# main.net
KiCad netlist of a schematic drawn in Altium Designer
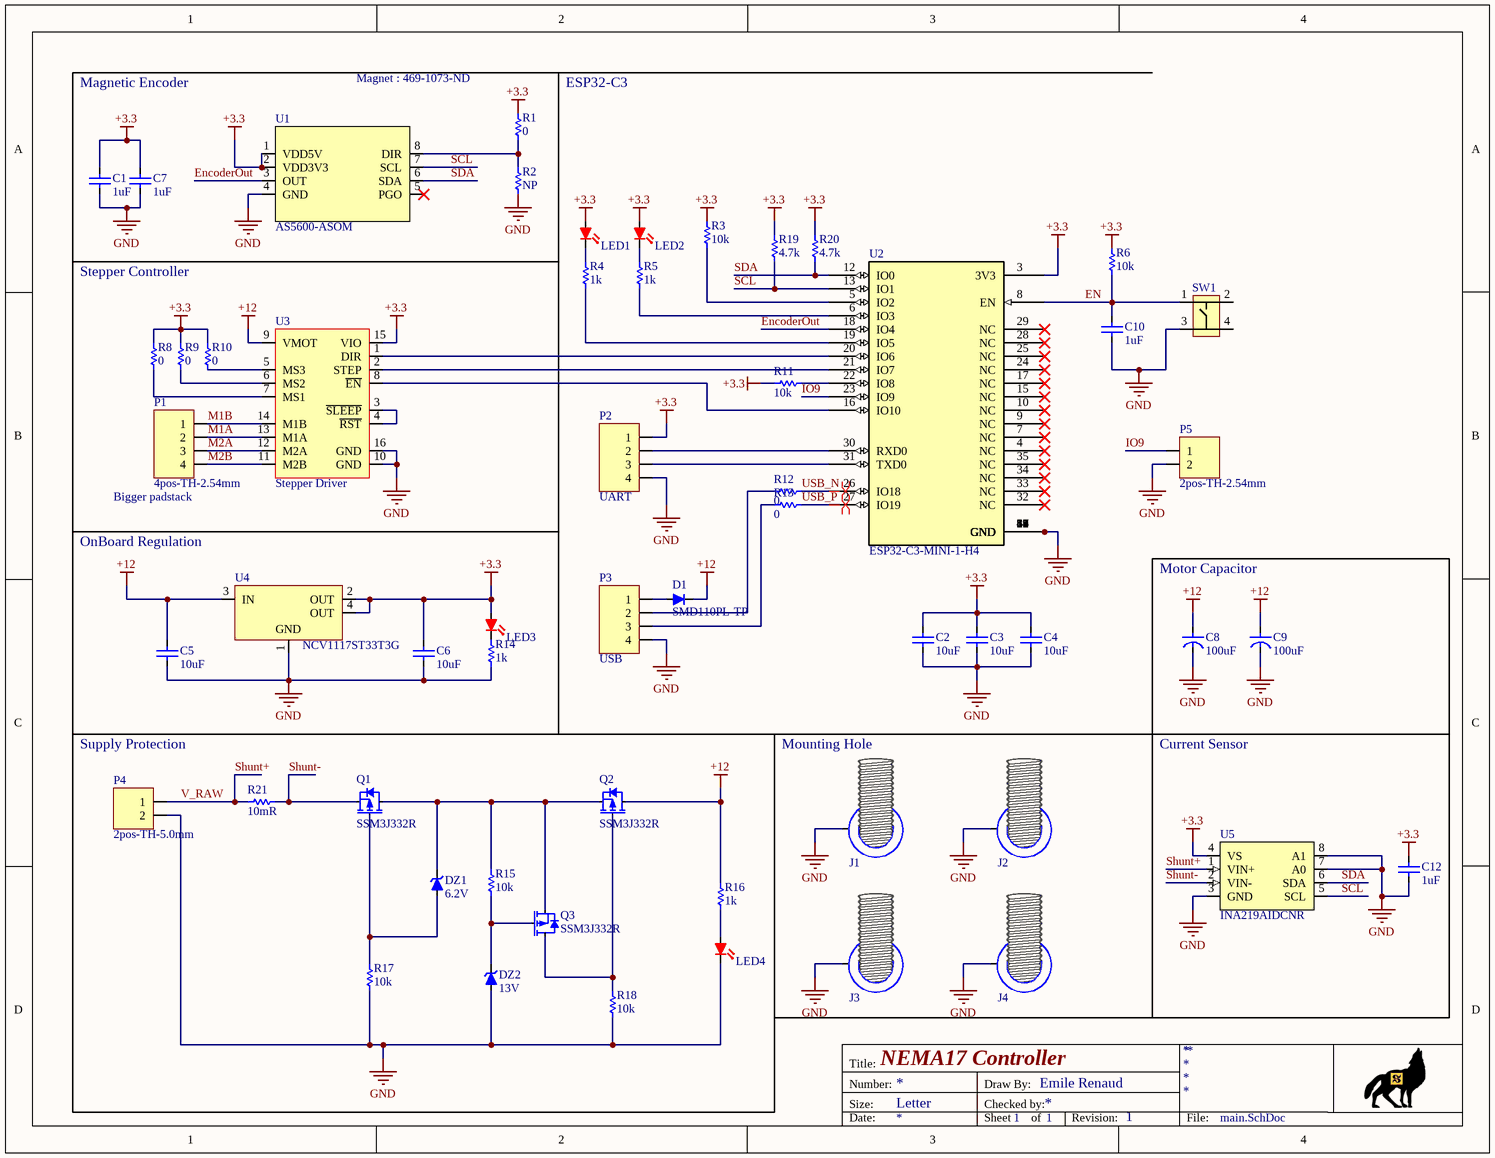
[diagram p0: main.SchDoc]

(export (version "E")
  (design (tool "Eeschema 10.0.6"))
  (components
    (comp (ref "C1")
      (value "1uF")
      (footprint "CAPACITOR-0603")
      (description "Capacitor-0603-1uF-25V-X5R")
      (libsource (lib "Capacitors") (part "Capacitor-0603-1uF-25V-X5R"))
    )
    (comp (ref "C2")
      (value "10uF")
      (footprint "CAPACITOR-0805")
      (description "Capacitor-0805-10uF-35V-X5R")
      (libsource (lib "Capacitors") (part "Capacitor-0805-10uF-35V-X5R"))
    )
    (comp (ref "C3")
      (value "10uF")
      (footprint "CAPACITOR-0805")
      (description "Capacitor-0805-10uF-35V-X5R")
      (libsource (lib "Capacitors") (part "Capacitor-0805-10uF-35V-X5R"))
    )
    (comp (ref "C4")
      (value "10uF")
      (footprint "CAPACITOR-0805")
      (description "Capacitor-0805-10uF-35V-X5R")
      (libsource (lib "Capacitors") (part "Capacitor-0805-10uF-35V-X5R"))
    )
    (comp (ref "C5")
      (value "10uF")
      (footprint "CAPACITOR-0805")
      (description "Capacitor-0805-10uF-35V-X5R")
      (libsource (lib "Capacitors") (part "Capacitor-0805-10uF-35V-X5R"))
    )
    (comp (ref "C6")
      (value "10uF")
      (footprint "CAPACITOR-0805")
      (description "Capacitor-0805-10uF-35V-X5R")
      (libsource (lib "Capacitors") (part "Capacitor-0805-10uF-35V-X5R"))
    )
    (comp (ref "C7")
      (value "1uF")
      (footprint "CAPACITOR-0603")
      (description "Capacitor-0603-1uF-25V-X5R")
      (libsource (lib "Capacitors") (part "Capacitor-0603-1uF-25V-X5R"))
    )
    (comp (ref "C8")
      (value "100uF")
      (footprint "CAPACITOR-Aluminium-5x11mm-2mmPitch")
      (description "CAP ALUM 100UF 20% 25V RADIAL")
      (libsource (lib "Capacitors-Electrolytic") (part "Capacitor-100uF-25V"))
    )
    (comp (ref "C9")
      (value "100uF")
      (footprint "CAPACITOR-Aluminium-5x11mm-2mmPitch")
      (description "CAP ALUM 100UF 20% 25V RADIAL")
      (libsource (lib "Capacitors-Electrolytic") (part "Capacitor-100uF-25V"))
    )
    (comp (ref "C10")
      (value "1uF")
      (footprint "CAPACITOR-0603")
      (description "Capacitor-0603-1uF-25V-X5R")
      (libsource (lib "Capacitors") (part "Capacitor-0603-1uF-25V-X5R"))
    )
    (comp (ref "C12")
      (value "1uF")
      (footprint "CAPACITOR-0603")
      (description "Capacitor-0603-1uF-25V-X5R")
      (libsource (lib "Capacitors") (part "Capacitor-0603-1uF-25V-X5R"))
    )
    (comp (ref "D1")
      (value "SMD110PL-TP")
      (footprint "SOD-123F")
      (description "DIODE SCHOTTKY 100V 1A SOD123FL")
      (libsource (lib "diodes") (part "SMD110PL-TP"))
    )
    (comp (ref "DZ1")
      (value "BZT52C6V2-TP")
      (footprint "SOD-123")
      (description "Zener Diode 6.2 V 200 mW ±6% Surface Mount SOD-123")
      (fields (field (name "VOLT") "6.2V"))
      (libsource (lib "diodes-zener") (part "BZT52C6V2-TP"))
    )
    (comp (ref "DZ2")
      (value "BZT52C13-TP")
      (footprint "SOD-123")
      (description "Zener Diode 13 V 200 mW ±6% Surface Mount SOD-123")
      (fields (field (name "VOLT") "13V"))
      (libsource (lib "diodes-zener") (part "BZT52C13-TP"))
    )
    (comp (ref "J1")
      (value "hole")
      (footprint "HOLE-3.40MM-M3-8MMEYELET")
      (description "Hole for M3 Bolt with 8mm pad")
      (libsource (lib "JumpersAndHoles") (part "Hole 3.40mm M3-Eyelet"))
    )
    (comp (ref "J2")
      (value "hole")
      (footprint "HOLE-3.40MM-M3-8MMEYELET")
      (description "Hole for M3 Bolt with 8mm pad")
      (libsource (lib "JumpersAndHoles") (part "Hole 3.40mm M3-Eyelet"))
    )
    (comp (ref "J3")
      (value "hole")
      (footprint "HOLE-3.40MM-M3-8MMEYELET")
      (description "Hole for M3 Bolt with 8mm pad")
      (libsource (lib "JumpersAndHoles") (part "Hole 3.40mm M3-Eyelet"))
    )
    (comp (ref "J4")
      (value "hole")
      (footprint "HOLE-3.40MM-M3-8MMEYELET")
      (description "Hole for M3 Bolt with 8mm pad")
      (libsource (lib "JumpersAndHoles") (part "Hole 3.40mm M3-Eyelet"))
    )
    (comp (ref "LED1")
      (value "B1911USD-20D000114U1930")
      (footprint "LED-0603-2PIN")
      (description "LED RED CLEAR 1608 SMD")
      (libsource (lib "LEDs") (part "B1911USD-20D000114U1930"))
    )
    (comp (ref "LED2")
      (value "B1911USD-20D000114U1930")
      (footprint "LED-0603-2PIN")
      (description "LED RED CLEAR 1608 SMD")
      (libsource (lib "LEDs") (part "B1911USD-20D000114U1930"))
    )
    (comp (ref "LED3")
      (value "B1911USD-20D000114U1930")
      (footprint "LED-0603-2PIN")
      (description "LED RED CLEAR 1608 SMD")
      (libsource (lib "LEDs") (part "B1911USD-20D000114U1930"))
    )
    (comp (ref "LED4")
      (value "B1911USD-20D000114U1930")
      (footprint "LED-0603-2PIN")
      (description "LED RED CLEAR 1608 SMD")
      (libsource (lib "LEDs") (part "B1911USD-20D000114U1930"))
    )
    (comp (ref "P1")
      (value "4pos-TH-2.54mm")
      (footprint "HDR1X4-W")
      (description "4pos TH 2.54mm Header")
      (libsource (lib "header") (part "4pos-TH-2.54mm"))
    )
    (comp (ref "P2")
      (value "UART")
      (footprint "HDR1X4")
      (description "4pos TH 2.54mm Header")
      (libsource (lib "header") (part "4pos-TH-2.54mm"))
    )
    (comp (ref "P3")
      (value "USB")
      (footprint "HDR1X4")
      (description "4pos TH 2.54mm Header")
      (libsource (lib "header") (part "4pos-TH-2.54mm"))
    )
    (comp (ref "P4")
      (value "2pos-TH-5.0mm")
      (footprint "Weco 2")
      (description "2pos-TH-5.0mm Screw Terminal")
      (libsource (lib "ScrewTerminal") (part "2pos-TH-5.0mm"))
    )
    (comp (ref "P5")
      (value "2pos-TH-2.54mm")
      (footprint "HDR1X2")
      (description "2pos TH 2.54mm Header")
      (libsource (lib "header") (part "2pos-TH-2.54mm"))
    )
    (comp (ref "Q1")
      (value "SSM3J332R")
      (footprint "SOT-23-3")
      (description "P-Channel 30 V 6A (Ta) 1W (Ta) Surface Mount SOT-23F")
      (libsource (lib "FET-P-Small") (part "SSM3J332R"))
    )
    (comp (ref "Q2")
      (value "SSM3J332R")
      (footprint "SOT-23-3")
      (description "P-Channel 30 V 6A (Ta) 1W (Ta) Surface Mount SOT-23F")
      (libsource (lib "FET-P-Small") (part "SSM3J332R"))
    )
    (comp (ref "Q3")
      (value "SSM3J332R")
      (footprint "SOT-23-3")
      (description "P-Channel 30 V 6A (Ta) 1W (Ta) Surface Mount SOT-23F")
      (libsource (lib "FET-P-Small") (part "SSM3J332R"))
    )
    (comp (ref "R1")
      (value "0")
      (footprint "Resistor-0603")
      (description "Resistor0603-0.0")
      (fields (field (name "Comment") "SMT resistor"))
      (libsource (lib "Resistors") (part "Resistor0603-0.0"))
    )
    (comp (ref "R2")
      (value "NP")
      (footprint "Resistor-0603")
      (description "Resistor0603-0.0")
      (fields (field (name "Comment") "SMT resistor"))
      (libsource (lib "Resistors") (part "Resistor0603-0.0"))
    )
    (comp (ref "R3")
      (value "10k")
      (footprint "Resistor-0603")
      (description "Resistor0603-10k")
      (fields (field (name "Comment") "SMT resistor"))
      (libsource (lib "Resistors") (part "Resistor0603-10k"))
    )
    (comp (ref "R4")
      (value "1k")
      (footprint "Resistor-0603")
      (description "Resistor0603-1k")
      (fields (field (name "Comment") "SMT resistor"))
      (libsource (lib "Resistors") (part "Resistor0603-1k"))
    )
    (comp (ref "R5")
      (value "1k")
      (footprint "Resistor-0603")
      (description "Resistor0603-1k")
      (fields (field (name "Comment") "SMT resistor"))
      (libsource (lib "Resistors") (part "Resistor0603-1k"))
    )
    (comp (ref "R6")
      (value "10k")
      (footprint "Resistor-0603")
      (description "Resistor0603-10k")
      (fields (field (name "Comment") "SMT resistor"))
      (libsource (lib "Resistors") (part "Resistor0603-10k"))
    )
    (comp (ref "R8")
      (value "0")
      (footprint "Resistor-0603")
      (description "Resistor0603-0.0")
      (fields (field (name "Comment") "SMT resistor"))
      (libsource (lib "Resistors") (part "Resistor0603-0.0"))
    )
    (comp (ref "R9")
      (value "0")
      (footprint "Resistor-0603")
      (description "Resistor0603-0.0")
      (fields (field (name "Comment") "SMT resistor"))
      (libsource (lib "Resistors") (part "Resistor0603-0.0"))
    )
    (comp (ref "R10")
      (value "0")
      (footprint "Resistor-0603")
      (description "Resistor0603-0.0")
      (fields (field (name "Comment") "SMT resistor"))
      (libsource (lib "Resistors") (part "Resistor0603-0.0"))
    )
    (comp (ref "R11")
      (value "10k")
      (footprint "Resistor-0603")
      (description "Resistor0603-10k")
      (fields (field (name "Comment") "SMT resistor"))
      (libsource (lib "Resistors") (part "Resistor0603-10k"))
    )
    (comp (ref "R12")
      (value "0")
      (footprint "Resistor-0603")
      (description "Resistor0603-0.0")
      (fields (field (name "Comment") "SMT resistor"))
      (libsource (lib "Resistors") (part "Resistor0603-0.0"))
    )
    (comp (ref "R13")
      (value "0")
      (footprint "Resistor-0603")
      (description "Resistor0603-0.0")
      (fields (field (name "Comment") "SMT resistor"))
      (libsource (lib "Resistors") (part "Resistor0603-0.0"))
    )
    (comp (ref "R14")
      (value "1k")
      (footprint "Resistor-0603")
      (description "Resistor0603-1k")
      (fields (field (name "Comment") "SMT resistor"))
      (libsource (lib "Resistors") (part "Resistor0603-1k"))
    )
    (comp (ref "R15")
      (value "10k")
      (footprint "Resistor-0603")
      (description "Resistor0603-10k")
      (fields (field (name "Comment") "SMT resistor"))
      (libsource (lib "Resistors") (part "Resistor0603-10k"))
    )
    (comp (ref "R16")
      (value "1k")
      (footprint "Resistor-0603")
      (description "Resistor0603-1k")
      (fields (field (name "Comment") "SMT resistor"))
      (libsource (lib "Resistors") (part "Resistor0603-1k"))
    )
    (comp (ref "R17")
      (value "10k")
      (footprint "Resistor-0603")
      (description "Resistor0603-10k")
      (fields (field (name "Comment") "SMT resistor"))
      (libsource (lib "Resistors") (part "Resistor0603-10k"))
    )
    (comp (ref "R18")
      (value "10k")
      (footprint "Resistor-0603")
      (description "Resistor0603-10k")
      (fields (field (name "Comment") "SMT resistor"))
      (libsource (lib "Resistors") (part "Resistor0603-10k"))
    )
    (comp (ref "R19")
      (value "4.7k")
      (footprint "Resistor-0603")
      (description "Resistor0603-4.7k")
      (fields (field (name "Comment") "SMT resistor"))
      (libsource (lib "Resistors") (part "Resistor0603-4.7k"))
    )
    (comp (ref "R20")
      (value "4.7k")
      (footprint "Resistor-0603")
      (description "Resistor0603-4.7k")
      (fields (field (name "Comment") "SMT resistor"))
      (libsource (lib "Resistors") (part "Resistor0603-4.7k"))
    )
    (comp (ref "R21")
      (value "10mR")
      (footprint "RESISTOR-1206")
      (description "Resistor1206-10mR")
      (fields (field (name "Comment") "SMT resistor"))
      (libsource (lib "Resistors") (part "Resistor1206-10mR"))
    )
    (comp (ref "SW1")
      (value "PTS815 SJM 250 SMTR LFS")
      (footprint "SW4_PTS815 SJM 250 SMTR LFS_CNK")
      (description "TACT 4.2 X 3.2, 2.5 MM H, 180GF,")
      (libsource (lib "THTPushButtonSwitches") (part "PTS815 SJM 250 SMTR LFS"))
    )
    (comp (ref "U1")
      (value "AS5600-ASOM")
      (footprint "AS5600L-ASOM_AMS")
      (description "SENSOR ANGLE 360DEG SMD")
      (fields
        (field (name "MANUFACTURER_PART_NUMBER") "AS5600L-ASOM")
        (field (name "COPYRIGHT") "Copyright (C) 2023 Ultra Librarian. All rights reserved.")
      )
      (libsource (lib "Encoder") (part "AS5600-ASOM"))
    )
    (comp (ref "U2")
      (value "ESP32-C3-MINI-1-H4")
      (footprint "ESP32-C3-MINI-1_EXP")
      (fields
        (field (name "MANUFACTURER_PART_NUMBER") "ESP32-C3-MINI-1-N4")
        (field (name "COPYRIGHT") "Copyright (C) 2023 Ultra Librarian. All rights reserved.")
      )
      (libsource (lib "Microcontrollers") (part "ESP32-C3-MINI-1-N4"))
    )
    (comp (ref "U3")
      (value "Stepper Driver")
      (footprint "A4899")
      (description "Stepper Driver PCB")
      (libsource (lib "MotorDrivers") (part "A4988"))
    )
    (comp (ref "U4")
      (value "NCV1117ST33T3G")
      (footprint "SOT-223-3/TO-261-3S")
      (description "IC REG LINEAR 3.3V 1A SOT223")
      (libsource (lib "PMIC-VoltageRegulators-LinearRegulators") (part "NCV1117ST33T3G"))
    )
    (comp (ref "U5")
      (value "INA219AIDCNR")
      (footprint "SOT-23-8")
      (description "IC CURRENT MONITOR 1% SOT23-8")
      (libsource (lib "PMIC-CurrentManagement") (part "INA219"))
    )
  )
  (nets
    (net (code "1") (name "+3.3") (class "Default")
      (node (ref "C1") (pin "2") (pinfunction "2_2") (pintype "passive"))
      (node (ref "C12") (pin "2") (pinfunction "2_2") (pintype "passive"))
      (node (ref "C2") (pin "2") (pinfunction "2_2") (pintype "passive"))
      (node (ref "C3") (pin "2") (pinfunction "2_2") (pintype "passive"))
      (node (ref "C4") (pin "2") (pinfunction "2_2") (pintype "passive"))
      (node (ref "C6") (pin "2") (pinfunction "2_2") (pintype "passive"))
      (node (ref "C7") (pin "2") (pinfunction "2_2") (pintype "passive"))
      (node (ref "LED1") (pin "2") (pinfunction "R_2") (pintype "passive"))
      (node (ref "LED2") (pin "2") (pinfunction "R_2") (pintype "passive"))
      (node (ref "LED3") (pin "2") (pinfunction "R_2") (pintype "passive"))
      (node (ref "P2") (pin "1") (pinfunction "1_1") (pintype "passive"))
      (node (ref "R1") (pin "2") (pinfunction "2_2") (pintype "passive"))
      (node (ref "R10") (pin "2") (pinfunction "2_2") (pintype "passive"))
      (node (ref "R11") (pin "2") (pinfunction "2_2") (pintype "passive"))
      (node (ref "R19") (pin "2") (pinfunction "2_2") (pintype "passive"))
      (node (ref "R20") (pin "2") (pinfunction "2_2") (pintype "passive"))
      (node (ref "R3") (pin "2") (pinfunction "2_2") (pintype "passive"))
      (node (ref "R6") (pin "2") (pinfunction "2_2") (pintype "passive"))
      (node (ref "R8") (pin "2") (pinfunction "2_2") (pintype "passive"))
      (node (ref "R9") (pin "2") (pinfunction "2_2") (pintype "passive"))
      (node (ref "U1") (pin "1") (pinfunction "VDD5V_1") (pintype "passive"))
      (node (ref "U1") (pin "2") (pinfunction "VDD3V3_2") (pintype "passive"))
      (node (ref "U2") (pin "3") (pinfunction "3V3_3") (pintype "power_in"))
      (node (ref "U3") (pin "15") (pinfunction "VIO_15") (pintype "passive"))
      (node (ref "U4") (pin "2") (pinfunction "OUT_2") (pintype "passive"))
      (node (ref "U4") (pin "4") (pinfunction "OUT_4") (pintype "passive"))
      (node (ref "U5") (pin "4") (pinfunction "VS_4") (pintype "power_in"))
    )
    (net (code "2") (name "+12") (class "Default")
      (node (ref "C5") (pin "2") (pinfunction "2_2") (pintype "passive"))
      (node (ref "C8") (pin "1") (pinfunction "1_1") (pintype "passive"))
      (node (ref "C9") (pin "1") (pinfunction "1_1") (pintype "passive"))
      (node (ref "D1") (pin "2") (pinfunction "K_2") (pintype "passive"))
      (node (ref "Q2") (pin "3") (pinfunction "D_3") (pintype "passive"))
      (node (ref "R16") (pin "2") (pinfunction "2_2") (pintype "passive"))
      (node (ref "U3") (pin "9") (pinfunction "VMOT_9") (pintype "passive"))
      (node (ref "U4") (pin "3") (pinfunction "IN_3") (pintype "passive"))
    )
    (net (code "3") (name "/EN") (class "Default")
      (node (ref "C10") (pin "2") (pinfunction "2_2") (pintype "passive"))
      (node (ref "R6") (pin "1") (pinfunction "1_1") (pintype "passive"))
      (node (ref "SW1") (pin "1") (pinfunction "1_1") (pintype "passive"))
      (node (ref "U2") (pin "8") (pinfunction "EN_8") (pintype "input"))
    )
    (net (code "4") (name "/EncoderOut") (class "Default")
      (node (ref "U1") (pin "3") (pinfunction "OUT_3") (pintype "passive"))
      (node (ref "U2") (pin "18") (pinfunction "IO4_18") (pintype "bidirectional"))
    )
    (net (code "5") (name "/IO9") (class "Default")
      (node (ref "P5") (pin "1") (pinfunction "1_1") (pintype "passive"))
      (node (ref "U2") (pin "23") (pinfunction "IO9_23") (pintype "bidirectional"))
    )
    (net (code "6") (name "/M1A") (class "Default")
      (node (ref "P1") (pin "2") (pinfunction "2_2") (pintype "passive"))
      (node (ref "U3") (pin "13") (pinfunction "M1A_13") (pintype "passive"))
    )
    (net (code "7") (name "/M1B") (class "Default")
      (node (ref "P1") (pin "1") (pinfunction "1_1") (pintype "passive"))
      (node (ref "U3") (pin "14") (pinfunction "M1B_14") (pintype "passive"))
    )
    (net (code "8") (name "/M2A") (class "Default")
      (node (ref "P1") (pin "3") (pinfunction "3_3") (pintype "passive"))
      (node (ref "U3") (pin "12") (pinfunction "M2A_12") (pintype "passive"))
    )
    (net (code "9") (name "/M2B") (class "Default")
      (node (ref "P1") (pin "4") (pinfunction "4_4") (pintype "passive"))
      (node (ref "U3") (pin "11") (pinfunction "M2B_11") (pintype "passive"))
    )
    (net (code "10") (name "/SCL") (class "Default")
      (node (ref "R19") (pin "1") (pinfunction "1_1") (pintype "passive"))
      (node (ref "U1") (pin "7") (pinfunction "SCL_7") (pintype "passive"))
      (node (ref "U2") (pin "13") (pinfunction "IO1_13") (pintype "bidirectional"))
      (node (ref "U5") (pin "5") (pinfunction "SCL_5") (pintype "passive"))
    )
    (net (code "11") (name "/SDA") (class "Default")
      (node (ref "R20") (pin "1") (pinfunction "1_1") (pintype "passive"))
      (node (ref "U1") (pin "6") (pinfunction "SDA_6") (pintype "passive"))
      (node (ref "U2") (pin "12") (pinfunction "IO0_12") (pintype "bidirectional"))
      (node (ref "U5") (pin "6") (pinfunction "SDA_6") (pintype "passive"))
    )
    (net (code "12") (name "/Shunt+") (class "Default")
      (node (ref "P4") (pin "1") (pinfunction "1_1") (pintype "passive"))
      (node (ref "R21") (pin "1") (pinfunction "1_1") (pintype "passive"))
      (node (ref "U5") (pin "1") (pinfunction "VIN+_1") (pintype "input"))
    )
    (net (code "13") (name "/Shunt-") (class "Default")
      (node (ref "Q1") (pin "2") (pinfunction "S_2") (pintype "passive"))
      (node (ref "R21") (pin "2") (pinfunction "2_2") (pintype "passive"))
      (node (ref "U5") (pin "2") (pinfunction "VIN-_2") (pintype "input"))
    )
    (net (code "14") (name "/USB_N") (class "Default")
      (node (ref "R12") (pin "2") (pinfunction "2_2") (pintype "passive"))
      (node (ref "U2") (pin "26") (pinfunction "IO18_26") (pintype "bidirectional"))
    )
    (net (code "15") (name "/USB_P") (class "Default")
      (node (ref "R13") (pin "2") (pinfunction "2_2") (pintype "passive"))
      (node (ref "U2") (pin "27") (pinfunction "IO19_27") (pintype "bidirectional"))
    )
    (net (code "16") (name "GND") (class "Default")
      (node (ref "C1") (pin "1") (pinfunction "1_1") (pintype "passive"))
      (node (ref "C10") (pin "1") (pinfunction "1_1") (pintype "passive"))
      (node (ref "C12") (pin "1") (pinfunction "1_1") (pintype "passive"))
      (node (ref "C2") (pin "1") (pinfunction "1_1") (pintype "passive"))
      (node (ref "C3") (pin "1") (pinfunction "1_1") (pintype "passive"))
      (node (ref "C4") (pin "1") (pinfunction "1_1") (pintype "passive"))
      (node (ref "C5") (pin "1") (pinfunction "1_1") (pintype "passive"))
      (node (ref "C6") (pin "1") (pinfunction "1_1") (pintype "passive"))
      (node (ref "C7") (pin "1") (pinfunction "1_1") (pintype "passive"))
      (node (ref "C8") (pin "2") (pinfunction "2_2") (pintype "passive"))
      (node (ref "C9") (pin "2") (pinfunction "2_2") (pintype "passive"))
      (node (ref "DZ2") (pin "1") (pinfunction "A_1") (pintype "passive"))
      (node (ref "J1") (pin "1") (pinfunction "1_1") (pintype "passive"))
      (node (ref "J2") (pin "1") (pinfunction "1_1") (pintype "passive"))
      (node (ref "J3") (pin "1") (pinfunction "1_1") (pintype "passive"))
      (node (ref "J4") (pin "1") (pinfunction "1_1") (pintype "passive"))
      (node (ref "LED4") (pin "1") (pinfunction "K_1") (pintype "passive"))
      (node (ref "P2") (pin "4") (pinfunction "4_4") (pintype "passive"))
      (node (ref "P3") (pin "4") (pinfunction "4_4") (pintype "passive"))
      (node (ref "P4") (pin "2") (pinfunction "2_2") (pintype "passive"))
      (node (ref "P5") (pin "2") (pinfunction "2_2") (pintype "passive"))
      (node (ref "R14") (pin "1") (pinfunction "1_1") (pintype "passive"))
      (node (ref "R17") (pin "1") (pinfunction "1_1") (pintype "passive"))
      (node (ref "R18") (pin "1") (pinfunction "1_1") (pintype "passive"))
      (node (ref "R2") (pin "1") (pinfunction "1_1") (pintype "passive"))
      (node (ref "SW1") (pin "3") (pinfunction "3_3") (pintype "passive"))
      (node (ref "U1") (pin "4") (pinfunction "GND_4") (pintype "passive"))
      (node (ref "U2") (pin "1") (pinfunction "GND_1") (pintype "passive"))
      (node (ref "U2") (pin "11") (pinfunction "GND_11") (pintype "passive"))
      (node (ref "U2") (pin "14") (pinfunction "GND_14") (pintype "passive"))
      (node (ref "U2") (pin "2") (pinfunction "GND_2") (pintype "passive"))
      (node (ref "U2") (pin "36") (pinfunction "GND_36") (pintype "passive"))
      (node (ref "U2") (pin "37") (pinfunction "GND_37") (pintype "passive"))
      (node (ref "U2") (pin "38") (pinfunction "GND_38") (pintype "passive"))
      (node (ref "U2") (pin "39") (pinfunction "GND_39") (pintype "passive"))
      (node (ref "U2") (pin "40") (pinfunction "GND_40") (pintype "passive"))
      (node (ref "U2") (pin "41") (pinfunction "GND_41") (pintype "passive"))
      (node (ref "U2") (pin "42") (pinfunction "GND_42") (pintype "passive"))
      (node (ref "U2") (pin "43") (pinfunction "GND_43") (pintype "passive"))
      (node (ref "U2") (pin "44") (pinfunction "GND_44") (pintype "passive"))
      (node (ref "U2") (pin "45") (pinfunction "GND_45") (pintype "passive"))
      (node (ref "U2") (pin "46") (pinfunction "GND_46") (pintype "passive"))
      (node (ref "U2") (pin "47") (pinfunction "GND_47") (pintype "passive"))
      (node (ref "U2") (pin "48") (pinfunction "GND_48") (pintype "passive"))
      (node (ref "U2") (pin "49") (pinfunction "GND_49") (pintype "passive"))
      (node (ref "U2") (pin "50") (pinfunction "GND_50") (pintype "passive"))
      (node (ref "U2") (pin "51") (pinfunction "GND_51") (pintype "passive"))
      (node (ref "U2") (pin "52") (pinfunction "GND_52") (pintype "passive"))
      (node (ref "U2") (pin "53") (pinfunction "GND_53") (pintype "passive"))
      (node (ref "U2") (pin "54") (pinfunction "GND_54") (pintype "passive"))
      (node (ref "U2") (pin "55") (pinfunction "GND_55") (pintype "passive"))
      (node (ref "U2") (pin "56") (pinfunction "GND_56") (pintype "passive"))
      (node (ref "U2") (pin "57") (pinfunction "GND_57") (pintype "passive"))
      (node (ref "U2") (pin "58") (pinfunction "GND_58") (pintype "passive"))
      (node (ref "U2") (pin "59") (pinfunction "GND_59") (pintype "passive"))
      (node (ref "U2") (pin "60") (pinfunction "GND_60") (pintype "passive"))
      (node (ref "U2") (pin "61") (pinfunction "GND_61") (pintype "passive"))
      (node (ref "U3") (pin "10") (pinfunction "GND_10") (pintype "passive"))
      (node (ref "U3") (pin "16") (pinfunction "GND_16") (pintype "passive"))
      (node (ref "U4") (pin "1") (pinfunction "GND_1") (pintype "passive"))
      (node (ref "U5") (pin "3") (pinfunction "GND_3") (pintype "power_in"))
      (node (ref "U5") (pin "7") (pinfunction "A0_7") (pintype "passive"))
      (node (ref "U5") (pin "8") (pinfunction "A1_8") (pintype "passive"))
    )
    (net (code "17") (name "Net-(D1-A)") (class "Default")
      (node (ref "D1") (pin "1") (pinfunction "A_1") (pintype "passive"))
      (node (ref "P3") (pin "1") (pinfunction "1_1") (pintype "passive"))
    )
    (net (code "18") (name "Net-(DZ1-A)") (class "Default")
      (node (ref "DZ1") (pin "1") (pinfunction "A_1") (pintype "passive"))
      (node (ref "Q1") (pin "1") (pinfunction "G_1") (pintype "passive"))
      (node (ref "R17") (pin "2") (pinfunction "2_2") (pintype "passive"))
    )
    (net (code "19") (name "Net-(DZ1-K)") (class "Default")
      (node (ref "DZ1") (pin "2") (pinfunction "K_2") (pintype "passive"))
      (node (ref "Q1") (pin "3") (pinfunction "D_3") (pintype "passive"))
      (node (ref "Q2") (pin "2") (pinfunction "S_2") (pintype "passive"))
      (node (ref "Q3") (pin "2") (pinfunction "S_2") (pintype "passive"))
      (node (ref "R15") (pin "2") (pinfunction "2_2") (pintype "passive"))
    )
    (net (code "20") (name "Net-(DZ2-K)") (class "Default")
      (node (ref "DZ2") (pin "2") (pinfunction "K_2") (pintype "passive"))
      (node (ref "Q3") (pin "1") (pinfunction "G_1") (pintype "passive"))
      (node (ref "R15") (pin "1") (pinfunction "1_1") (pintype "passive"))
    )
    (net (code "21") (name "Net-(LED1-K)") (class "Default")
      (node (ref "LED1") (pin "1") (pinfunction "K_1") (pintype "passive"))
      (node (ref "R4") (pin "2") (pinfunction "2_2") (pintype "passive"))
    )
    (net (code "22") (name "Net-(LED2-K)") (class "Default")
      (node (ref "LED2") (pin "1") (pinfunction "K_1") (pintype "passive"))
      (node (ref "R5") (pin "2") (pinfunction "2_2") (pintype "passive"))
    )
    (net (code "23") (name "Net-(LED3-K)") (class "Default")
      (node (ref "LED3") (pin "1") (pinfunction "K_1") (pintype "passive"))
      (node (ref "R14") (pin "2") (pinfunction "2_2") (pintype "passive"))
    )
    (net (code "24") (name "Net-(LED4-R)") (class "Default")
      (node (ref "LED4") (pin "2") (pinfunction "R_2") (pintype "passive"))
      (node (ref "R16") (pin "1") (pinfunction "1_1") (pintype "passive"))
    )
    (net (code "25") (name "Net-(P3-Pad2)") (class "Default")
      (node (ref "P3") (pin "2") (pinfunction "2_2") (pintype "passive"))
      (node (ref "R12") (pin "1") (pinfunction "1_1") (pintype "passive"))
    )
    (net (code "26") (name "Net-(P3-Pad3)") (class "Default")
      (node (ref "P3") (pin "3") (pinfunction "3_3") (pintype "passive"))
      (node (ref "R13") (pin "1") (pinfunction "1_1") (pintype "passive"))
    )
    (net (code "27") (name "Net-(Q2-G)") (class "Default")
      (node (ref "Q2") (pin "1") (pinfunction "G_1") (pintype "passive"))
      (node (ref "Q3") (pin "3") (pinfunction "D_3") (pintype "passive"))
      (node (ref "R18") (pin "2") (pinfunction "2_2") (pintype "passive"))
    )
    (net (code "28") (name "Net-(U1-DIR)") (class "Default")
      (node (ref "R1") (pin "1") (pinfunction "1_1") (pintype "passive"))
      (node (ref "R2") (pin "2") (pinfunction "2_2") (pintype "passive"))
      (node (ref "U1") (pin "8") (pinfunction "DIR_8") (pintype "passive"))
    )
    (net (code "29") (name "Net-(U2-IO2)") (class "Default")
      (node (ref "R3") (pin "1") (pinfunction "1_1") (pintype "passive"))
      (node (ref "U2") (pin "5") (pinfunction "IO2_5") (pintype "bidirectional"))
    )
    (net (code "30") (name "Net-(U2-IO3)") (class "Default")
      (node (ref "R5") (pin "1") (pinfunction "1_1") (pintype "passive"))
      (node (ref "U2") (pin "6") (pinfunction "IO3_6") (pintype "bidirectional"))
    )
    (net (code "31") (name "Net-(U2-IO5)") (class "Default")
      (node (ref "R4") (pin "1") (pinfunction "1_1") (pintype "passive"))
      (node (ref "U2") (pin "19") (pinfunction "IO5_19") (pintype "bidirectional"))
    )
    (net (code "32") (name "Net-(U2-IO6)") (class "Default")
      (node (ref "U2") (pin "20") (pinfunction "IO6_20") (pintype "bidirectional"))
      (node (ref "U3") (pin "1") (pinfunction "DIR_1") (pintype "passive"))
    )
    (net (code "33") (name "Net-(U2-IO7)") (class "Default")
      (node (ref "U2") (pin "21") (pinfunction "IO7_21") (pintype "bidirectional"))
      (node (ref "U3") (pin "2") (pinfunction "STEP_2") (pintype "passive"))
    )
    (net (code "34") (name "Net-(U2-IO8)") (class "Default")
      (node (ref "R11") (pin "1") (pinfunction "1_1") (pintype "passive"))
      (node (ref "U2") (pin "22") (pinfunction "IO8_22") (pintype "bidirectional"))
    )
    (net (code "35") (name "Net-(U2-IO10)") (class "Default")
      (node (ref "U2") (pin "16") (pinfunction "IO10_16") (pintype "bidirectional"))
      (node (ref "U3") (pin "8") (pinfunction "~{EN}_8") (pintype "passive"))
    )
    (net (code "36") (name "Net-(U2-RXD0)") (class "Default")
      (node (ref "P2") (pin "2") (pinfunction "2_2") (pintype "passive"))
      (node (ref "U2") (pin "30") (pinfunction "RXD0_30") (pintype "bidirectional"))
    )
    (net (code "37") (name "Net-(U2-TXD0)") (class "Default")
      (node (ref "P2") (pin "3") (pinfunction "3_3") (pintype "passive"))
      (node (ref "U2") (pin "31") (pinfunction "TXD0_31") (pintype "bidirectional"))
    )
    (net (code "38") (name "Net-(U3-MS1)") (class "Default")
      (node (ref "R8") (pin "1") (pinfunction "1_1") (pintype "passive"))
      (node (ref "U3") (pin "7") (pinfunction "MS1_7") (pintype "passive"))
    )
    (net (code "39") (name "Net-(U3-MS2)") (class "Default")
      (node (ref "R9") (pin "1") (pinfunction "1_1") (pintype "passive"))
      (node (ref "U3") (pin "6") (pinfunction "MS2_6") (pintype "passive"))
    )
    (net (code "40") (name "Net-(U3-MS3)") (class "Default")
      (node (ref "R10") (pin "1") (pinfunction "1_1") (pintype "passive"))
      (node (ref "U3") (pin "5") (pinfunction "MS3_5") (pintype "passive"))
    )
    (net (code "41") (name "Net-(U3-~{RST})") (class "Default")
      (node (ref "U3") (pin "3") (pinfunction "~{SLEEP}_3") (pintype "passive"))
      (node (ref "U3") (pin "4") (pinfunction "~{RST}_4") (pintype "passive"))
    )
    (net (code "42") (name "unconnected-(SW1-Pad2)") (class "Default")
      (node (ref "SW1") (pin "2") (pinfunction "2_2") (pintype "passive"))
    )
    (net (code "43") (name "unconnected-(SW1-Pad4)") (class "Default")
      (node (ref "SW1") (pin "4") (pinfunction "4_4") (pintype "passive"))
    )
    (net (code "44") (name "unconnected-(U1-PGO-Pad5)") (class "Default")
      (node (ref "U1") (pin "5") (pinfunction "PGO_5") (pintype "passive+no_connect"))
    )
    (net (code "45") (name "unconnected-(U2-NC-Pad4)") (class "Default")
      (node (ref "U2") (pin "4") (pinfunction "NC_4") (pintype "passive+no_connect"))
    )
    (net (code "46") (name "unconnected-(U2-NC-Pad7)") (class "Default")
      (node (ref "U2") (pin "7") (pinfunction "NC_7") (pintype "passive+no_connect"))
    )
    (net (code "47") (name "unconnected-(U2-NC-Pad9)") (class "Default")
      (node (ref "U2") (pin "9") (pinfunction "NC_9") (pintype "passive+no_connect"))
    )
    (net (code "48") (name "unconnected-(U2-NC-Pad10)") (class "Default")
      (node (ref "U2") (pin "10") (pinfunction "NC_10") (pintype "passive+no_connect"))
    )
    (net (code "49") (name "unconnected-(U2-NC-Pad15)") (class "Default")
      (node (ref "U2") (pin "15") (pinfunction "NC_15") (pintype "passive+no_connect"))
    )
    (net (code "50") (name "unconnected-(U2-NC-Pad17)") (class "Default")
      (node (ref "U2") (pin "17") (pinfunction "NC_17") (pintype "passive+no_connect"))
    )
    (net (code "51") (name "unconnected-(U2-NC-Pad24)") (class "Default")
      (node (ref "U2") (pin "24") (pinfunction "NC_24") (pintype "passive+no_connect"))
    )
    (net (code "52") (name "unconnected-(U2-NC-Pad25)") (class "Default")
      (node (ref "U2") (pin "25") (pinfunction "NC_25") (pintype "passive+no_connect"))
    )
    (net (code "53") (name "unconnected-(U2-NC-Pad28)") (class "Default")
      (node (ref "U2") (pin "28") (pinfunction "NC_28") (pintype "passive+no_connect"))
    )
    (net (code "54") (name "unconnected-(U2-NC-Pad29)") (class "Default")
      (node (ref "U2") (pin "29") (pinfunction "NC_29") (pintype "passive+no_connect"))
    )
    (net (code "55") (name "unconnected-(U2-NC-Pad32)") (class "Default")
      (node (ref "U2") (pin "32") (pinfunction "NC_32") (pintype "passive+no_connect"))
    )
    (net (code "56") (name "unconnected-(U2-NC-Pad33)") (class "Default")
      (node (ref "U2") (pin "33") (pinfunction "NC_33") (pintype "passive+no_connect"))
    )
    (net (code "57") (name "unconnected-(U2-NC-Pad34)") (class "Default")
      (node (ref "U2") (pin "34") (pinfunction "NC_34") (pintype "passive+no_connect"))
    )
    (net (code "58") (name "unconnected-(U2-NC-Pad35)") (class "Default")
      (node (ref "U2") (pin "35") (pinfunction "NC_35") (pintype "passive+no_connect"))
    )
  )
)
